# Tarjeta2.net
KiCad netlist of a schematic drawn in EAGLE
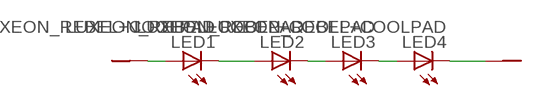
[diagram p0: schematic, sheet 1]

(export (version "E")
  (design (tool "Eeschema 10.0.6"))
  (components
    (comp (ref "LED1")
      (value "LUXEON_REBEL+COOLPAD")
      (footprint "eagle-import:LUXEON_REBEL+COOLPAD")
      (libsource (lib "eagle-import") (part "LUXEON_REBEL+COOLPAD"))
    )
    (comp (ref "LED2")
      (value "LUXEON_REBEL+COOLPAD")
      (footprint "eagle-import:LUXEON_REBEL+COOLPAD")
      (libsource (lib "eagle-import") (part "LUXEON_REBEL+COOLPAD"))
    )
    (comp (ref "LED3")
      (value "LUXEON_REBEL+COOLPAD")
      (footprint "eagle-import:LUXEON_REBEL+COOLPAD")
      (libsource (lib "eagle-import") (part "LUXEON_REBEL+COOLPAD"))
    )
    (comp (ref "LED4")
      (value "LUXEON_REBEL+COOLPAD")
      (footprint "eagle-import:LUXEON_REBEL+COOLPAD")
      (libsource (lib "eagle-import") (part "LUXEON_REBEL+COOLPAD"))
    )
    (comp (ref "U$1")
      (value "POWER_PIN")
      (footprint "eagle-import:POWER_PIN")
      (libsource (lib "eagle-import") (part "POWER_PIN"))
    )
    (comp (ref "U$2")
      (value "POWER_PIN")
      (footprint "eagle-import:POWER_PIN")
      (libsource (lib "eagle-import") (part "POWER_PIN"))
    )
  )
  (nets
    (net (code "1") (name "Net-(LED1-PadA)") (class "Default")
      (node (ref "LED1") (pin "A") (pinfunction "A_A") (pintype "passive"))
      (node (ref "LED1") (pin "A@1") (pinfunction "A_A@1") (pintype "passive"))
      (node (ref "U$1") (pin "P$1") (pinfunction "P$1_P$1") (pintype "bidirectional"))
    )
    (net (code "2") (name "Net-(LED1-PadC)") (class "Default")
      (node (ref "LED1") (pin "C") (pinfunction "C_C") (pintype "passive"))
      (node (ref "LED1") (pin "C@1") (pinfunction "C_C@1") (pintype "passive"))
      (node (ref "LED2") (pin "A") (pinfunction "A_A") (pintype "passive"))
      (node (ref "LED2") (pin "A@1") (pinfunction "A_A@1") (pintype "passive"))
    )
    (net (code "3") (name "Net-(LED2-PadC)") (class "Default")
      (node (ref "LED2") (pin "C") (pinfunction "C_C") (pintype "passive"))
      (node (ref "LED2") (pin "C@1") (pinfunction "C_C@1") (pintype "passive"))
      (node (ref "LED3") (pin "A") (pinfunction "A_A") (pintype "passive"))
      (node (ref "LED3") (pin "A@1") (pinfunction "A_A@1") (pintype "passive"))
    )
    (net (code "4") (name "Net-(LED3-PadC)") (class "Default")
      (node (ref "LED3") (pin "C") (pinfunction "C_C") (pintype "passive"))
      (node (ref "LED3") (pin "C@1") (pinfunction "C_C@1") (pintype "passive"))
      (node (ref "LED4") (pin "A") (pinfunction "A_A") (pintype "passive"))
      (node (ref "LED4") (pin "A@1") (pinfunction "A_A@1") (pintype "passive"))
    )
    (net (code "5") (name "Net-(LED4-PadC)") (class "Default")
      (node (ref "LED4") (pin "C") (pinfunction "C_C") (pintype "passive"))
      (node (ref "LED4") (pin "C@1") (pinfunction "C_C@1") (pintype "passive"))
      (node (ref "U$2") (pin "P$1") (pinfunction "P$1_P$1") (pintype "bidirectional"))
    )
  )
)
